# Copy_of_HandHeld_Terminal.net
KiCad netlist of a schematic drawn in Altium Designer
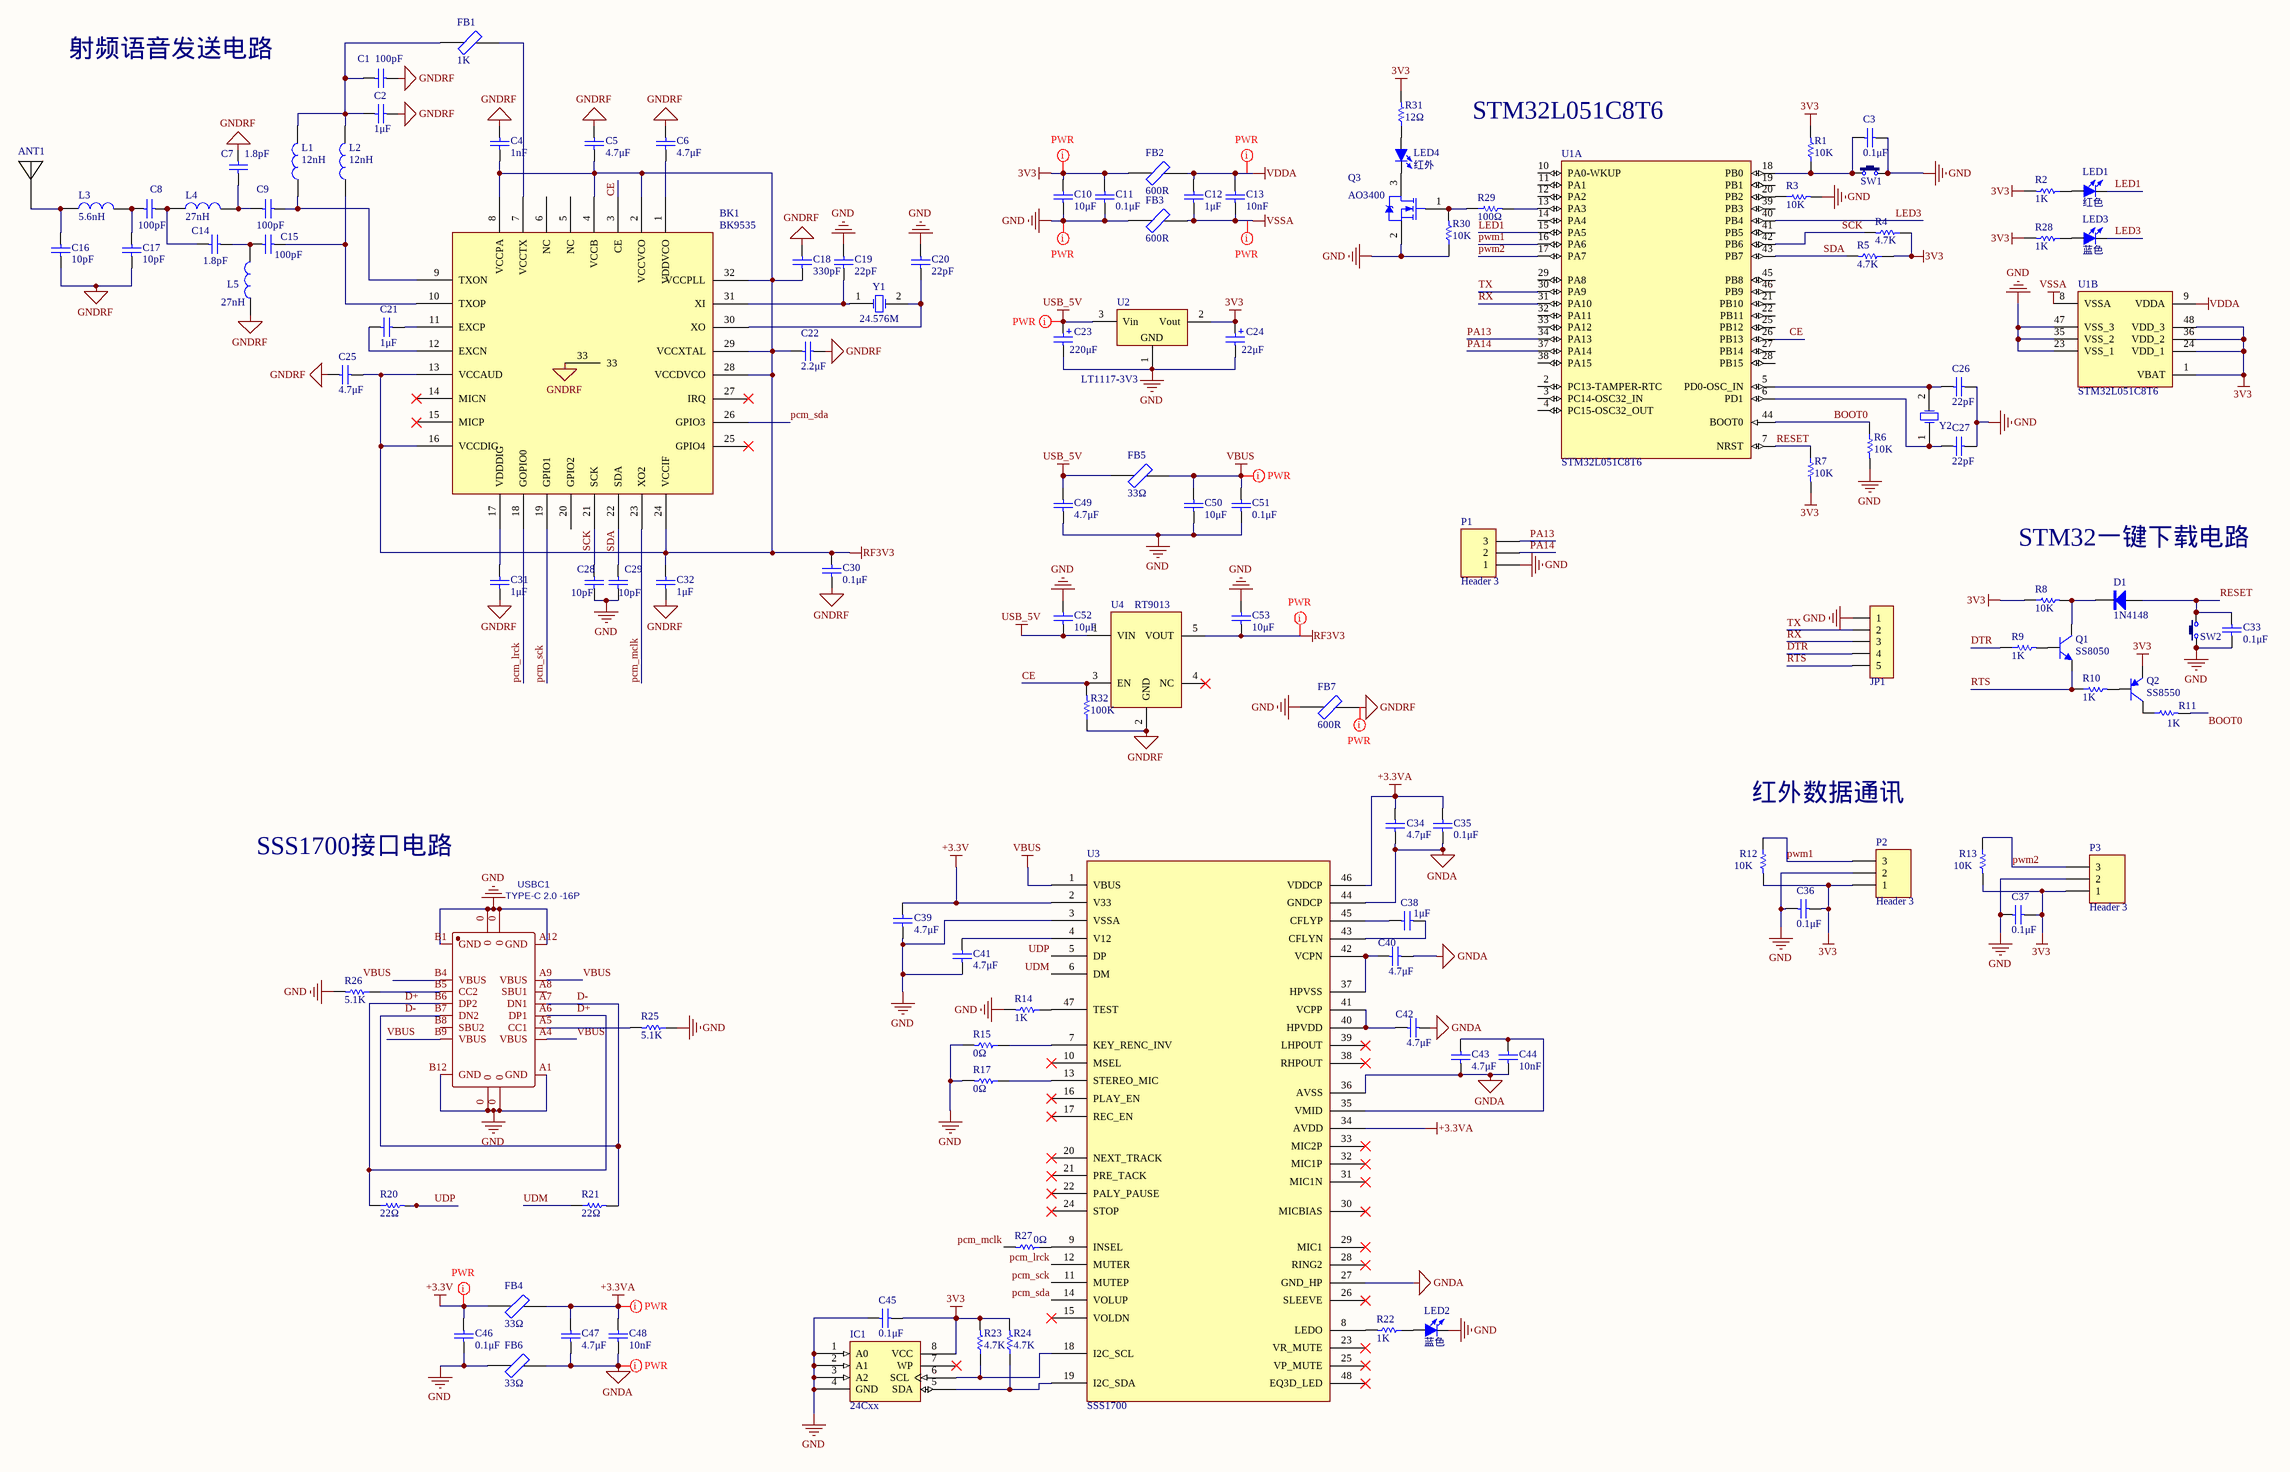
[diagram p0: Copy of HandHeld_Terminal.SchDoc]

(export (version "E")
  (design (tool "Eeschema 10.0.6"))
  (components
    (comp (ref "ANT1")
      (value "~")
      (footprint "ANT")
      (description "PCB板载天线")
      (fields (field (name "版权归属") "源创客"))
      (libsource (lib "手持发射端") (part "ANT1"))
    )
    (comp (ref "BK1") (value "BK9535") (footprint "QFN32 5x5_N") (libsource (lib "Nixie") (part "BK9530")))
    (comp (ref "C1")
      (value "100pF")
      (footprint "C 0603_L")
      (description "Capacitor")
      (fields (field (name "Comment") "Cap") (field (name "PUBLISHER") "Altium Limited"))
      (libsource (lib "Nixie") (part "Cap"))
    )
    (comp (ref "C2")
      (value "1μF")
      (footprint "C 0805_L")
      (description "Capacitor")
      (fields (field (name "Comment") "Cap") (field (name "PUBLISHER") "Altium Limited"))
      (libsource (lib "Nixie") (part "Cap"))
    )
    (comp (ref "C3")
      (value "0.1μF")
      (footprint "C 0805_L")
      (description "Capacitor")
      (fields (field (name "Comment") "Cap") (field (name "PUBLISHER") "Altium Limited"))
      (libsource (lib "Nixie") (part "Cap"))
    )
    (comp (ref "C4")
      (value "1nF")
      (footprint "C 0805_L")
      (description "Capacitor")
      (fields (field (name "Comment") "Cap") (field (name "PUBLISHER") "Altium Limited"))
      (libsource (lib "Nixie") (part "Cap"))
    )
    (comp (ref "C5")
      (value "4.7μF")
      (footprint "C 0805_L")
      (description "Capacitor")
      (fields (field (name "Comment") "Cap") (field (name "PUBLISHER") "Altium Limited"))
      (libsource (lib "Nixie") (part "Cap"))
    )
    (comp (ref "C6")
      (value "4.7μF")
      (footprint "C 0805_L")
      (description "Capacitor")
      (fields (field (name "Comment") "Cap") (field (name "PUBLISHER") "Altium Limited"))
      (libsource (lib "Nixie") (part "Cap"))
    )
    (comp (ref "C7")
      (value "1.8pF")
      (footprint "C 0603_L")
      (description "Capacitor")
      (fields (field (name "Comment") "Cap") (field (name "PUBLISHER") "Altium Limited"))
      (libsource (lib "Nixie") (part "Cap"))
    )
    (comp (ref "C8")
      (value "100pF")
      (footprint "C 0603_L")
      (description "Capacitor")
      (fields (field (name "Comment") "Cap") (field (name "PUBLISHER") "Altium Limited"))
      (libsource (lib "Nixie") (part "Cap"))
    )
    (comp (ref "C9")
      (value "100pF")
      (footprint "C 0603_L")
      (description "Capacitor")
      (fields (field (name "Comment") "Cap") (field (name "PUBLISHER") "Altium Limited"))
      (libsource (lib "Nixie") (part "Cap"))
    )
    (comp (ref "C10")
      (value "10μF")
      (footprint "C 0805_L")
      (description "Capacitor")
      (fields (field (name "Comment") "Cap") (field (name "PUBLISHER") "Altium Limited"))
      (libsource (lib "Nixie") (part "Cap"))
    )
    (comp (ref "C11")
      (value "0.1μF")
      (footprint "C 0805_L")
      (description "Capacitor")
      (fields (field (name "Comment") "Cap") (field (name "PUBLISHER") "Altium Limited"))
      (libsource (lib "Nixie") (part "Cap"))
    )
    (comp (ref "C12")
      (value "1μF")
      (footprint "C 0805_L")
      (description "Capacitor")
      (fields (field (name "Comment") "Cap") (field (name "PUBLISHER") "Altium Limited"))
      (libsource (lib "Nixie") (part "Cap"))
    )
    (comp (ref "C13")
      (value "10nF")
      (footprint "C 0805_L")
      (description "Capacitor")
      (fields (field (name "Comment") "Cap") (field (name "PUBLISHER") "Altium Limited"))
      (libsource (lib "Nixie") (part "Cap"))
    )
    (comp (ref "C14")
      (value "1.8pF")
      (footprint "C 0603_L")
      (description "Capacitor")
      (fields (field (name "Comment") "Cap") (field (name "PUBLISHER") "Altium Limited"))
      (libsource (lib "Nixie") (part "Cap"))
    )
    (comp (ref "C15")
      (value "100pF")
      (footprint "C 0603_L")
      (description "Capacitor")
      (fields (field (name "Comment") "Cap") (field (name "PUBLISHER") "Altium Limited"))
      (libsource (lib "Nixie") (part "Cap"))
    )
    (comp (ref "C16")
      (value "10pF")
      (footprint "C 0603_L")
      (description "Capacitor")
      (fields (field (name "Comment") "Cap") (field (name "PUBLISHER") "Altium Limited"))
      (libsource (lib "Nixie") (part "Cap"))
    )
    (comp (ref "C17")
      (value "10pF")
      (footprint "C 0603_L")
      (description "Capacitor")
      (fields (field (name "Comment") "Cap") (field (name "PUBLISHER") "Altium Limited"))
      (libsource (lib "Nixie") (part "Cap"))
    )
    (comp (ref "C18")
      (value "330pF")
      (footprint "C 0805_L")
      (description "Capacitor")
      (fields (field (name "Comment") "Cap") (field (name "PUBLISHER") "Altium Limited"))
      (libsource (lib "Nixie") (part "Cap"))
    )
    (comp (ref "C19")
      (value "22pF")
      (footprint "C 0805_L")
      (description "Capacitor")
      (fields (field (name "Comment") "Cap") (field (name "PUBLISHER") "Altium Limited"))
      (libsource (lib "Nixie") (part "Cap"))
    )
    (comp (ref "C20")
      (value "22pF")
      (footprint "C 0805_L")
      (description "Capacitor")
      (fields (field (name "Comment") "Cap") (field (name "PUBLISHER") "Altium Limited"))
      (libsource (lib "Nixie") (part "Cap"))
    )
    (comp (ref "C21")
      (value "1μF")
      (footprint "C 0805_L")
      (description "Capacitor")
      (fields (field (name "Comment") "Cap") (field (name "PUBLISHER") "Altium Limited"))
      (libsource (lib "Nixie") (part "Cap"))
    )
    (comp (ref "C22")
      (value "2.2μF")
      (footprint "C 0805_L")
      (description "Capacitor")
      (fields (field (name "Comment") "Cap") (field (name "PUBLISHER") "Altium Limited"))
      (libsource (lib "Nixie") (part "Cap"))
    )
    (comp (ref "C23")
      (value "220μF")
      (footprint "CM D(6.3*5.4)")
      (description "Polarized Capacitor (Radial)")
      (fields (field (name "Comment") "Cap Pol1") (field (name "PUBLISHER") "Altium Limited"))
      (libsource (lib "Nixie") (part "Cap Pol1"))
    )
    (comp (ref "C24")
      (value "22μF")
      (footprint "CD C(6032)")
      (description "Polarized Capacitor (Radial)")
      (fields (field (name "Comment") "Cap Pol1") (field (name "PUBLISHER") "Altium Limited"))
      (libsource (lib "Nixie") (part "Cap Pol1"))
    )
    (comp (ref "C25")
      (value "4.7μF")
      (footprint "C 0805_L")
      (description "Capacitor")
      (fields (field (name "Comment") "Cap") (field (name "PUBLISHER") "Altium Limited"))
      (libsource (lib "Nixie") (part "Cap"))
    )
    (comp (ref "C26")
      (value "22pF")
      (footprint "C 0805_L")
      (description "Capacitor")
      (fields (field (name "Comment") "Cap") (field (name "PUBLISHER") "Altium Limited"))
      (libsource (lib "Nixie") (part "Cap"))
    )
    (comp (ref "C27")
      (value "22pF")
      (footprint "C 0805_L")
      (description "Capacitor")
      (fields (field (name "Comment") "Cap") (field (name "PUBLISHER") "Altium Limited"))
      (libsource (lib "Nixie") (part "Cap"))
    )
    (comp (ref "C28")
      (value "10pF")
      (footprint "C 0603_L")
      (description "Capacitor")
      (fields (field (name "Comment") "Cap") (field (name "PUBLISHER") "Altium Limited"))
      (libsource (lib "Nixie") (part "Cap"))
    )
    (comp (ref "C29")
      (value "10pF")
      (footprint "C 0603_L")
      (description "Capacitor")
      (fields (field (name "Comment") "Cap") (field (name "PUBLISHER") "Altium Limited"))
      (libsource (lib "Nixie") (part "Cap"))
    )
    (comp (ref "C30")
      (value "0.1μF")
      (footprint "C 0805_L")
      (description "Capacitor")
      (fields (field (name "Comment") "Cap") (field (name "PUBLISHER") "Altium Limited"))
      (libsource (lib "Nixie") (part "Cap"))
    )
    (comp (ref "C31")
      (value "1μF")
      (footprint "C 0805_L")
      (description "Capacitor")
      (fields (field (name "Comment") "Cap") (field (name "PUBLISHER") "Altium Limited"))
      (libsource (lib "Nixie") (part "Cap"))
    )
    (comp (ref "C32")
      (value "1μF")
      (footprint "C 0805_L")
      (description "Capacitor")
      (fields (field (name "Comment") "Cap") (field (name "PUBLISHER") "Altium Limited"))
      (libsource (lib "Nixie") (part "Cap"))
    )
    (comp (ref "C33")
      (value "0.1μF")
      (footprint "C 0805_L")
      (description "Capacitor")
      (fields (field (name "Comment") "Cap") (field (name "PUBLISHER") "Altium Limited"))
      (libsource (lib "Nixie") (part "Cap"))
    )
    (comp (ref "C34")
      (value "4.7μF")
      (footprint "C 0805_L")
      (description "Capacitor")
      (fields (field (name "Comment") "Cap") (field (name "PUBLISHER") "Altium Limited"))
      (libsource (lib "Nixie") (part "Cap"))
    )
    (comp (ref "C35")
      (value "0.1μF")
      (footprint "C 0805_L")
      (description "Capacitor")
      (fields (field (name "Comment") "Cap") (field (name "PUBLISHER") "Altium Limited"))
      (libsource (lib "Nixie") (part "Cap"))
    )
    (comp (ref "C36")
      (value "0.1μF")
      (footprint "C 0805_L")
      (description "Capacitor")
      (fields (field (name "Comment") "Cap") (field (name "PUBLISHER") "Altium Limited"))
      (libsource (lib "Nixie") (part "Cap"))
    )
    (comp (ref "C37")
      (value "0.1μF")
      (footprint "C 0805_L")
      (description "Capacitor")
      (fields (field (name "Comment") "Cap") (field (name "PUBLISHER") "Altium Limited"))
      (libsource (lib "Nixie") (part "Cap"))
    )
    (comp (ref "C38")
      (value "1μF")
      (footprint "C 0805_L")
      (description "Capacitor")
      (fields (field (name "Comment") "Cap") (field (name "PUBLISHER") "Altium Limited"))
      (libsource (lib "Nixie") (part "Cap"))
    )
    (comp (ref "C39")
      (value "4.7μF")
      (footprint "C 0805_L")
      (description "Capacitor")
      (fields (field (name "Comment") "Cap") (field (name "PUBLISHER") "Altium Limited"))
      (libsource (lib "Nixie") (part "Cap"))
    )
    (comp (ref "C40")
      (value "4.7μF")
      (footprint "C 0805_L")
      (description "Capacitor")
      (fields (field (name "Comment") "Cap") (field (name "PUBLISHER") "Altium Limited"))
      (libsource (lib "Nixie") (part "Cap"))
    )
    (comp (ref "C41")
      (value "4.7μF")
      (footprint "C 0805_L")
      (description "Capacitor")
      (fields (field (name "Comment") "Cap") (field (name "PUBLISHER") "Altium Limited"))
      (libsource (lib "Nixie") (part "Cap"))
    )
    (comp (ref "C42")
      (value "4.7μF")
      (footprint "C 0805_L")
      (description "Capacitor")
      (fields (field (name "Comment") "Cap") (field (name "PUBLISHER") "Altium Limited"))
      (libsource (lib "Nixie") (part "Cap"))
    )
    (comp (ref "C43")
      (value "4.7μF")
      (footprint "C 0805_L")
      (description "Capacitor")
      (fields (field (name "Comment") "Cap") (field (name "PUBLISHER") "Altium Limited"))
      (libsource (lib "Nixie") (part "Cap"))
    )
    (comp (ref "C44")
      (value "10nF")
      (footprint "C 0805_L")
      (description "Capacitor")
      (fields (field (name "Comment") "Cap") (field (name "PUBLISHER") "Altium Limited"))
      (libsource (lib "Nixie") (part "Cap"))
    )
    (comp (ref "C45")
      (value "0.1μF")
      (footprint "C 0805_L")
      (description "Capacitor")
      (fields (field (name "Comment") "Cap") (field (name "PUBLISHER") "Altium Limited"))
      (libsource (lib "Nixie") (part "Cap"))
    )
    (comp (ref "C46")
      (value "0.1μF")
      (footprint "C 0805_L")
      (description "Capacitor")
      (fields (field (name "Comment") "Cap") (field (name "PUBLISHER") "Altium Limited"))
      (libsource (lib "Nixie") (part "Cap"))
    )
    (comp (ref "C47")
      (value "4.7μF")
      (footprint "C 0805_L")
      (description "Capacitor")
      (fields (field (name "Comment") "Cap") (field (name "PUBLISHER") "Altium Limited"))
      (libsource (lib "Nixie") (part "Cap"))
    )
    (comp (ref "C48")
      (value "10nF")
      (footprint "C 0805_L")
      (description "Capacitor")
      (fields (field (name "Comment") "Cap") (field (name "PUBLISHER") "Altium Limited"))
      (libsource (lib "Nixie") (part "Cap"))
    )
    (comp (ref "C49")
      (value "4.7μF")
      (footprint "C 0805_L")
      (description "Capacitor")
      (fields (field (name "Comment") "Cap") (field (name "PUBLISHER") "Altium Limited"))
      (libsource (lib "Nixie") (part "Cap"))
    )
    (comp (ref "C50")
      (value "10μF")
      (footprint "C 0805_L")
      (description "Capacitor")
      (fields (field (name "Comment") "Cap") (field (name "PUBLISHER") "Altium Limited"))
      (libsource (lib "Nixie") (part "Cap"))
    )
    (comp (ref "C51")
      (value "0.1μF")
      (footprint "C 0805_L")
      (description "Capacitor")
      (fields (field (name "Comment") "Cap") (field (name "PUBLISHER") "Altium Limited"))
      (libsource (lib "Nixie") (part "Cap"))
    )
    (comp (ref "C52")
      (value "10μF")
      (footprint "C 0805_L")
      (description "Capacitor")
      (fields (field (name "Comment") "Cap") (field (name "PUBLISHER") "Altium Limited"))
      (libsource (lib "Nixie") (part "Cap"))
    )
    (comp (ref "C53")
      (value "10μF")
      (footprint "C 0805_L")
      (description "Capacitor")
      (fields (field (name "Comment") "Cap") (field (name "PUBLISHER") "Altium Limited"))
      (libsource (lib "Nixie") (part "Cap"))
    )
    (comp (ref "D1")
      (value "1N4148")
      (footprint "SOD-323")
      (description "开关二极管")
      (libsource (lib "Nixie") (part "1N4148"))
    )
    (comp (ref "FB1")
      (value "1K")
      (footprint "C 0603_L")
      (description "铁氧体磁珠")
      (fields (field (name "Comment") "Ferrite bead"))
      (libsource (lib "Nixie") (part "Ferrite bead"))
    )
    (comp (ref "FB2")
      (value "600R")
      (footprint "C 0603_L")
      (description "铁氧体磁珠")
      (fields (field (name "Comment") "Ferrite bead"))
      (libsource (lib "Nixie") (part "Ferrite bead"))
    )
    (comp (ref "FB3")
      (value "600R")
      (footprint "C 0603_L")
      (description "铁氧体磁珠")
      (fields (field (name "Comment") "Ferrite bead"))
      (libsource (lib "Nixie") (part "Ferrite bead"))
    )
    (comp (ref "FB4")
      (value "33Ω")
      (footprint "C 0603_L")
      (description "铁氧体磁珠")
      (fields (field (name "Comment") "Ferrite bead"))
      (libsource (lib "Nixie") (part "Ferrite bead"))
    )
    (comp (ref "FB5")
      (value "33Ω")
      (footprint "C 0603_L")
      (description "铁氧体磁珠")
      (fields (field (name "Comment") "Ferrite bead"))
      (libsource (lib "Nixie") (part "Ferrite bead"))
    )
    (comp (ref "FB6")
      (value "33Ω")
      (footprint "C 0603_L")
      (description "铁氧体磁珠")
      (fields (field (name "Comment") "Ferrite bead"))
      (libsource (lib "Nixie") (part "Ferrite bead"))
    )
    (comp (ref "FB7")
      (value "600R")
      (footprint "C 0603_L")
      (description "铁氧体磁珠")
      (fields (field (name "Comment") "Ferrite bead"))
      (libsource (lib "Nixie") (part "Ferrite bead"))
    )
    (comp (ref "IC1")
      (value "24Cxx")
      (footprint "SOP8_L")
      (description "外置EEPROM")
      (fields (field (name "版权归属") "封装库来自淘宝 ID：黄晶宝石"))
      (libsource (lib "Nixie") (part "24Cxx"))
    )
    (comp (ref "JP1")
      (value "HDR-1X5")
      (footprint "HDR2.0-LI-5P")
      (description "5P接插件")
      (fields (field (name "版权归属") "封装库来自淘宝 ID：黄晶宝石"))
      (libsource (lib "Nixie") (part "Header 5"))
    )
    (comp (ref "L1")
      (value "12nH")
      (footprint "L 0603")
      (description "小功率贴片电感")
      (fields (field (name "Comment") "L"))
      (libsource (lib "Nixie") (part "L"))
    )
    (comp (ref "L2")
      (value "12nH")
      (footprint "L 0603")
      (description "小功率贴片电感")
      (fields (field (name "Comment") "L"))
      (libsource (lib "Nixie") (part "L"))
    )
    (comp (ref "L3")
      (value "5.6nH")
      (footprint "L 0603")
      (description "小功率贴片电感")
      (fields (field (name "Comment") "L"))
      (libsource (lib "Nixie") (part "L"))
    )
    (comp (ref "L4")
      (value "27nH")
      (footprint "L 0603")
      (description "小功率贴片电感")
      (fields (field (name "Comment") "L"))
      (libsource (lib "Nixie") (part "L"))
    )
    (comp (ref "L5")
      (value "27nH")
      (footprint "L 0603")
      (description "小功率贴片电感")
      (fields (field (name "Comment") "L"))
      (libsource (lib "Nixie") (part "L"))
    )
    (comp (ref "LED1")
      (value "红色")
      (footprint "LED 0805R")
      (description "贴片LED")
      (fields (field (name "版权归属") "封装库来自淘宝 ID：黄晶宝石"))
      (libsource (lib "Nixie") (part "LED-SMD"))
    )
    (comp (ref "LED2")
      (value "蓝色")
      (footprint "LED 0805B")
      (description "贴片LED")
      (fields (field (name "版权归属") "封装库来自淘宝 ID：黄晶宝石"))
      (libsource (lib "Nixie") (part "LED-SMD"))
    )
    (comp (ref "LED3")
      (value "蓝色")
      (footprint "LED 0805B")
      (description "贴片LED")
      (fields (field (name "版权归属") "封装库来自淘宝 ID：黄晶宝石"))
      (libsource (lib "Nixie") (part "LED-SMD"))
    )
    (comp (ref "LED4")
      (value "红外")
      (footprint "LED 3MM-R")
      (description "贴片LED")
      (fields (field (name "版权归属") "封装库来自淘宝 ID：黄晶宝石"))
      (libsource (lib "Nixie") (part "LED-SMD"))
    )
    (comp (ref "P1")
      (value "Header 3")
      (footprint "HDR1X3")
      (description "Header, 3-Pin")
      (fields (field (name "PUBLISHER") "Altium Limited"))
      (libsource (lib "Miscellaneous Connectors") (part "Header 3"))
    )
    (comp (ref "P2")
      (value "Header 3")
      (footprint "HDR1X3")
      (description "Header, 3-Pin")
      (fields (field (name "PUBLISHER") "Altium Limited"))
      (libsource (lib "") (part "Header 3_1"))
    )
    (comp (ref "P3")
      (value "Header 3")
      (footprint "HDR1X3")
      (description "Header, 3-Pin")
      (fields (field (name "PUBLISHER") "Altium Limited"))
      (libsource (lib "") (part "Header 3_1"))
    )
    (comp (ref "Q1")
      (value "SS8050")
      (footprint "SOT-23-3L")
      (description "高频放大-NPN型")
      (fields (field (name "版权归属") "封装库来自淘宝 ID：黄晶宝石"))
      (libsource (lib "Nixie") (part "8050-SMD"))
    )
    (comp (ref "Q2")
      (value "SS8550")
      (footprint "SOT-23-3L")
      (description "高频放大-PNP型")
      (fields (field (name "版权归属") "封装库来自淘宝 ID：黄晶宝石"))
      (libsource (lib "Nixie") (part "8550-SMD"))
    )
    (comp (ref "Q3")
      (value "AO3400")
      (footprint "SOT-23-3L")
      (description "N-Channel Power MOSFET")
      (fields (field (name "PUBLISHER") "Altium Limited"))
      (libsource (lib "Nixie") (part "NMOS-2"))
    )
    (comp (ref "R1")
      (value "10K")
      (footprint "R 0805_L")
      (description "Resistor")
      (fields (field (name "PUBLISHER") "Altium Limited"))
      (libsource (lib "Nixie") (part "Resistor"))
    )
    (comp (ref "R2")
      (value "1K")
      (footprint "R 0805_L")
      (description "Resistor")
      (fields (field (name "PUBLISHER") "Altium Limited"))
      (libsource (lib "Nixie") (part "Resistor"))
    )
    (comp (ref "R3")
      (value "10K")
      (footprint "R 0805_L")
      (description "Resistor")
      (fields (field (name "PUBLISHER") "Altium Limited"))
      (libsource (lib "Nixie") (part "Resistor"))
    )
    (comp (ref "R4")
      (value "4.7K")
      (footprint "R 0805_L")
      (description "Resistor")
      (fields (field (name "PUBLISHER") "Altium Limited"))
      (libsource (lib "Nixie") (part "Resistor"))
    )
    (comp (ref "R5")
      (value "4.7K")
      (footprint "R 0805_L")
      (description "Resistor")
      (fields (field (name "PUBLISHER") "Altium Limited"))
      (libsource (lib "Nixie") (part "Resistor"))
    )
    (comp (ref "R6")
      (value "10K")
      (footprint "R 0805_L")
      (description "Resistor")
      (fields (field (name "PUBLISHER") "Altium Limited"))
      (libsource (lib "Nixie") (part "Resistor"))
    )
    (comp (ref "R7")
      (value "10K")
      (footprint "R 0805_L")
      (description "Resistor")
      (fields (field (name "PUBLISHER") "Altium Limited"))
      (libsource (lib "Nixie") (part "Resistor"))
    )
    (comp (ref "R8")
      (value "10K")
      (footprint "R 0805_L")
      (description "Resistor")
      (fields (field (name "PUBLISHER") "Altium Limited"))
      (libsource (lib "Nixie") (part "Resistor"))
    )
    (comp (ref "R9")
      (value "1K")
      (footprint "R 0805_L")
      (description "Resistor")
      (fields (field (name "PUBLISHER") "Altium Limited"))
      (libsource (lib "Nixie") (part "Resistor"))
    )
    (comp (ref "R10")
      (value "1K")
      (footprint "R 0805_L")
      (description "Resistor")
      (fields (field (name "PUBLISHER") "Altium Limited"))
      (libsource (lib "Nixie") (part "Resistor"))
    )
    (comp (ref "R11")
      (value "1K")
      (footprint "R 0805_L")
      (description "Resistor")
      (fields (field (name "PUBLISHER") "Altium Limited"))
      (libsource (lib "Nixie") (part "Resistor"))
    )
    (comp (ref "R12")
      (value "10K")
      (footprint "R 0805_L")
      (description "Resistor")
      (fields (field (name "PUBLISHER") "Altium Limited"))
      (libsource (lib "Nixie") (part "Resistor"))
    )
    (comp (ref "R13")
      (value "10K")
      (footprint "R 0805_L")
      (description "Resistor")
      (fields (field (name "PUBLISHER") "Altium Limited"))
      (libsource (lib "Nixie") (part "Resistor"))
    )
    (comp (ref "R14")
      (value "1K")
      (footprint "R 0805_L")
      (description "Resistor")
      (fields (field (name "PUBLISHER") "Altium Limited"))
      (libsource (lib "Nixie") (part "Resistor"))
    )
    (comp (ref "R15")
      (value "0Ω")
      (footprint "R 0603_L")
      (description "Resistor")
      (fields (field (name "PUBLISHER") "Altium Limited"))
      (libsource (lib "Nixie") (part "Resistor"))
    )
    (comp (ref "R17")
      (value "0Ω")
      (footprint "R 0603_L")
      (description "Resistor")
      (fields (field (name "PUBLISHER") "Altium Limited"))
      (libsource (lib "Nixie") (part "Resistor"))
    )
    (comp (ref "R20")
      (value "22Ω")
      (footprint "R 0603_L")
      (description "Resistor")
      (fields (field (name "PUBLISHER") "Altium Limited"))
      (libsource (lib "Nixie") (part "Resistor"))
    )
    (comp (ref "R21")
      (value "22Ω")
      (footprint "R 0603_L")
      (description "Resistor")
      (fields (field (name "PUBLISHER") "Altium Limited"))
      (libsource (lib "Nixie") (part "Resistor"))
    )
    (comp (ref "R22")
      (value "1K")
      (footprint "R 0805_L")
      (description "Resistor")
      (fields (field (name "PUBLISHER") "Altium Limited"))
      (libsource (lib "Nixie") (part "Resistor"))
    )
    (comp (ref "R23")
      (value "4.7K")
      (footprint "R 0805_L")
      (description "Resistor")
      (fields (field (name "PUBLISHER") "Altium Limited"))
      (libsource (lib "Nixie") (part "Resistor"))
    )
    (comp (ref "R24")
      (value "4.7K")
      (footprint "R 0805_L")
      (description "Resistor")
      (fields (field (name "PUBLISHER") "Altium Limited"))
      (libsource (lib "Nixie") (part "Resistor"))
    )
    (comp (ref "R25")
      (value "5.1K")
      (footprint "R 0805_L")
      (description "Resistor")
      (fields (field (name "PUBLISHER") "Altium Limited"))
      (libsource (lib "Nixie") (part "Resistor"))
    )
    (comp (ref "R26")
      (value "5.1K")
      (footprint "R 0805_L")
      (description "Resistor")
      (fields (field (name "PUBLISHER") "Altium Limited"))
      (libsource (lib "Nixie") (part "Resistor"))
    )
    (comp (ref "R27")
      (value "0Ω")
      (footprint "R 0603_L")
      (description "Resistor")
      (fields (field (name "PUBLISHER") "Altium Limited"))
      (libsource (lib "Nixie") (part "Resistor"))
    )
    (comp (ref "R28")
      (value "1K")
      (footprint "R 0805_L")
      (description "Resistor")
      (fields (field (name "PUBLISHER") "Altium Limited"))
      (libsource (lib "Nixie") (part "Resistor"))
    )
    (comp (ref "R29")
      (value "100Ω")
      (footprint "R 0805_L")
      (description "Resistor")
      (fields (field (name "PUBLISHER") "Altium Limited"))
      (libsource (lib "Nixie") (part "Resistor"))
    )
    (comp (ref "R30")
      (value "10K")
      (footprint "R 0805_L")
      (description "Resistor")
      (fields (field (name "PUBLISHER") "Altium Limited"))
      (libsource (lib "Nixie") (part "Resistor"))
    )
    (comp (ref "R31")
      (value "12Ω")
      (footprint "R 1210_L")
      (description "Resistor")
      (fields (field (name "PUBLISHER") "Altium Limited"))
      (libsource (lib "Nixie") (part "Resistor"))
    )
    (comp (ref "R32")
      (value "100K")
      (footprint "R 0805_L")
      (description "Resistor")
      (fields (field (name "PUBLISHER") "Altium Limited"))
      (libsource (lib "Nixie") (part "Resistor"))
    )
    (comp (ref "SW1")
      (value "3x6x5")
      (footprint "TSW SMD-3*6*2.5")
      (description "3x6轻触开关")
      (fields (field (name "版权归属") "封装库来自淘宝 ID：黄晶宝石"))
      (libsource (lib "") (part "TSW 3x6_1"))
    )
    (comp (ref "SW2")
      (value "3x6x5")
      (footprint "TSW SMD-3*6*2.5")
      (description "3x6轻触开关")
      (fields (field (name "版权归属") "封装库来自淘宝 ID：黄晶宝石"))
      (libsource (lib "Nixie") (part "TSW 3x6"))
    )
    (comp (ref "U1")
      (value "STM32L051C8T6")
      (footprint "LQFP48_L")
      (description "ARM")
      (libsource (lib "Nixie") (part "STM32F103C8T6"))
    )
    (comp (ref "U2")
      (value "LT1117-3V3")
      (footprint "SOT223_L")
      (description "三端稳压芯片")
      (fields (field (name "版权归属") "源创客"))
      (libsource (lib "Nixie") (part "LT1117"))
    )
    (comp (ref "U3")
      (value "SSS1700")
      (footprint "LQFP48_L")
      (description "USB音频芯片")
      (libsource (lib "Nixie") (part "SSS1700"))
    )
    (comp (ref "U4")
      (value "RT9013")
      (footprint "SOT23-5L")
      (description "LDO")
      (libsource (lib "HandHeld_terminal") (part "RT9013"))
    )
    (comp (ref "USBC1")
      (value "TYPE-C 2.0 -16P")
      (footprint "USB-C-SMD_TYPE-C-USB-5")
      (description "USB2.0 Type-C 母座 16Pin")
      (libsource (lib "Nixie") (part "USB2.0 Type-C 16Pin母座"))
    )
    (comp (ref "Y1")
      (value "24.576M")
      (footprint "OSC 5032-2P")
      (description "Crystal Oscillator")
      (fields (field (name "PUBLISHER") "Altium Limited"))
      (libsource (lib "Miscellaneous Devices") (part "XTAL"))
    )
    (comp (ref "Y2")
      (value "8MHz ±20ppm 20pF")
      (footprint "OSC 5032-2P")
      (description "贴片晶振")
      (libsource (lib "HandHeld_terminal") (part "SMD-5032_2P 8MHz 20ppm 20pF"))
    )
  )
  (nets
    (net (code "1") (name "+3.3V") (class "Default")
      (node (ref "C39") (pin "2") (pinfunction "2_2") (pintype "passive"))
      (node (ref "C46") (pin "2") (pinfunction "2_2") (pintype "passive"))
      (node (ref "FB4") (pin "1") (pinfunction "1_1") (pintype "passive"))
      (node (ref "U3") (pin "2") (pinfunction "V33_2") (pintype "passive"))
    )
    (net (code "2") (name "+3.3VA") (class "Default")
      (node (ref "C34") (pin "2") (pinfunction "2_2") (pintype "passive"))
      (node (ref "C35") (pin "2") (pinfunction "2_2") (pintype "passive"))
      (node (ref "C47") (pin "2") (pinfunction "2_2") (pintype "passive"))
      (node (ref "C48") (pin "2") (pinfunction "2_2") (pintype "passive"))
      (node (ref "FB4") (pin "2") (pinfunction "2_2") (pintype "passive"))
      (node (ref "U3") (pin "34") (pinfunction "AVDD_34") (pintype "passive"))
      (node (ref "U3") (pin "46") (pinfunction "VDDCP_46") (pintype "passive"))
    )
    (net (code "3") (name "/BOOT0") (class "Default")
      (node (ref "R11") (pin "2") (pinfunction "2_2") (pintype "passive"))
      (node (ref "R6") (pin "1") (pinfunction "1_1") (pintype "passive"))
      (node (ref "U1") (pin "44") (pinfunction "BOOT0_44") (pintype "input"))
    )
    (net (code "4") (name "/CE") (class "Default")
      (node (ref "BK1") (pin "3") (pinfunction "CE_3") (pintype "passive"))
      (node (ref "R32") (pin "2") (pinfunction "2_2") (pintype "passive"))
      (node (ref "U1") (pin "26") (pinfunction "PB13_26") (pintype "bidirectional"))
      (node (ref "U4") (pin "3") (pinfunction "EN_3") (pintype "passive"))
    )
    (net (code "5") (name "/D+") (class "Default")
      (node (ref "R20") (pin "1") (pinfunction "1_1") (pintype "passive"))
      (node (ref "USBC1") (pin "A6") (pinfunction "DP1_A6") (pintype "passive"))
      (node (ref "USBC1") (pin "B6") (pinfunction "DP2_B6") (pintype "passive"))
    )
    (net (code "6") (name "/D-") (class "Default")
      (node (ref "R21") (pin "2") (pinfunction "2_2") (pintype "passive"))
      (node (ref "USBC1") (pin "A7") (pinfunction "DN1_A7") (pintype "passive"))
      (node (ref "USBC1") (pin "B7") (pinfunction "DN2_B7") (pintype "passive"))
    )
    (net (code "7") (name "/DTR") (class "Default")
      (node (ref "JP1") (pin "4") (pinfunction "4_4") (pintype "passive"))
      (node (ref "R9") (pin "1") (pinfunction "1_1") (pintype "passive"))
    )
    (net (code "8") (name "/LED1") (class "Default")
      (node (ref "LED1") (pin "2") (pinfunction "K_2") (pintype "passive"))
      (node (ref "U1") (pin "15") (pinfunction "PA5_15") (pintype "bidirectional"))
    )
    (net (code "9") (name "/LED3") (class "Default")
      (node (ref "LED3") (pin "2") (pinfunction "K_2") (pintype "passive"))
      (node (ref "U1") (pin "40") (pinfunction "PB4_40") (pintype "bidirectional"))
    )
    (net (code "10") (name "/PA13") (class "Default")
      (node (ref "P1") (pin "3") (pinfunction "3_3") (pintype "passive"))
      (node (ref "U1") (pin "34") (pinfunction "PA13_34") (pintype "bidirectional"))
    )
    (net (code "11") (name "/PA14") (class "Default")
      (node (ref "P1") (pin "2") (pinfunction "2_2") (pintype "passive"))
      (node (ref "U1") (pin "37") (pinfunction "PA14_37") (pintype "bidirectional"))
    )
    (net (code "12") (name "/RESET") (class "Default")
      (node (ref "C33") (pin "2") (pinfunction "2_2") (pintype "passive"))
      (node (ref "D1") (pin "1") (pinfunction "A_1") (pintype "passive"))
      (node (ref "R7") (pin "1") (pinfunction "1_1") (pintype "passive"))
      (node (ref "SW2") (pin "2") (pinfunction "2_2") (pintype "passive"))
      (node (ref "U1") (pin "7") (pinfunction "NRST_7") (pintype "bidirectional"))
    )
    (net (code "13") (name "/RTS") (class "Default")
      (node (ref "JP1") (pin "5") (pinfunction "5_5") (pintype "passive"))
      (node (ref "Q1") (pin "2") (pinfunction "E_2") (pintype "passive"))
      (node (ref "R10") (pin "1") (pinfunction "1_1") (pintype "passive"))
    )
    (net (code "14") (name "/RX") (class "Default")
      (node (ref "JP1") (pin "3") (pinfunction "3_3") (pintype "passive"))
      (node (ref "U1") (pin "31") (pinfunction "PA10_31") (pintype "bidirectional"))
    )
    (net (code "15") (name "/SCK") (class "Default")
      (node (ref "BK1") (pin "21") (pinfunction "SCK_21") (pintype "passive"))
      (node (ref "C28") (pin "2") (pinfunction "2_2") (pintype "passive"))
      (node (ref "R4") (pin "2") (pinfunction "2_2") (pintype "passive"))
      (node (ref "U1") (pin "42") (pinfunction "PB6_42") (pintype "bidirectional"))
    )
    (net (code "16") (name "/SDA") (class "Default")
      (node (ref "BK1") (pin "22") (pinfunction "SDA_22") (pintype "passive"))
      (node (ref "C29") (pin "2") (pinfunction "2_2") (pintype "passive"))
      (node (ref "R5") (pin "2") (pinfunction "2_2") (pintype "passive"))
      (node (ref "U1") (pin "43") (pinfunction "PB7_43") (pintype "bidirectional"))
    )
    (net (code "17") (name "/TX") (class "Default")
      (node (ref "JP1") (pin "2") (pinfunction "2_2") (pintype "passive"))
      (node (ref "U1") (pin "30") (pinfunction "PA9_30") (pintype "bidirectional"))
    )
    (net (code "18") (name "/UDM") (class "Default")
      (node (ref "R21") (pin "1") (pinfunction "1_1") (pintype "passive"))
      (node (ref "U3") (pin "6") (pinfunction "DM_6") (pintype "passive"))
    )
    (net (code "19") (name "/UDP") (class "Default")
      (node (ref "R20") (pin "2") (pinfunction "2_2") (pintype "passive"))
      (node (ref "U3") (pin "5") (pinfunction "DP_5") (pintype "passive"))
    )
    (net (code "20") (name "/pcm_lrck") (class "Default")
      (node (ref "BK1") (pin "18") (pinfunction "GOPIO0_18") (pintype "passive"))
      (node (ref "U3") (pin "12") (pinfunction "MUTER_12") (pintype "passive"))
    )
    (net (code "21") (name "/pcm_mclk") (class "Default")
      (node (ref "BK1") (pin "23") (pinfunction "XO2_23") (pintype "passive"))
      (node (ref "R27") (pin "2") (pinfunction "2_2") (pintype "passive"))
    )
    (net (code "22") (name "/pcm_sck") (class "Default")
      (node (ref "BK1") (pin "19") (pinfunction "GPIO1_19") (pintype "passive"))
      (node (ref "U3") (pin "11") (pinfunction "MUTEP_11") (pintype "passive"))
    )
    (net (code "23") (name "/pcm_sda") (class "Default")
      (node (ref "BK1") (pin "26") (pinfunction "GPIO3_26") (pintype "passive"))
      (node (ref "U3") (pin "14") (pinfunction "VOLUP_14") (pintype "passive"))
    )
    (net (code "24") (name "/pwm1") (class "Default")
      (node (ref "P2") (pin "3") (pinfunction "3_3") (pintype "passive"))
      (node (ref "R12") (pin "1") (pinfunction "1_1") (pintype "passive"))
      (node (ref "U1") (pin "16") (pinfunction "PA6_16") (pintype "bidirectional"))
    )
    (net (code "25") (name "/pwm2") (class "Default")
      (node (ref "P3") (pin "3") (pinfunction "3_3") (pintype "passive"))
      (node (ref "R13") (pin "1") (pinfunction "1_1") (pintype "passive"))
      (node (ref "U1") (pin "17") (pinfunction "PA7_17") (pintype "bidirectional"))
    )
    (net (code "26") (name "3V3") (class "Default")
      (node (ref "C10") (pin "2") (pinfunction "2_2") (pintype "passive"))
      (node (ref "C11") (pin "2") (pinfunction "2_2") (pintype "passive"))
      (node (ref "C24") (pin "1") (pinfunction "1_1") (pintype "passive"))
      (node (ref "C36") (pin "1") (pinfunction "1_1") (pintype "passive"))
      (node (ref "C37") (pin "1") (pinfunction "1_1") (pintype "passive"))
      (node (ref "C45") (pin "1") (pinfunction "1_1") (pintype "passive"))
      (node (ref "FB2") (pin "1") (pinfunction "1_1") (pintype "passive"))
      (node (ref "IC1") (pin "8") (pinfunction "VCC_8") (pintype "power_in"))
      (node (ref "P2") (pin "1") (pinfunction "1_1") (pintype "passive"))
      (node (ref "P3") (pin "1") (pinfunction "1_1") (pintype "passive"))
      (node (ref "Q2") (pin "2") (pinfunction "E_2") (pintype "passive"))
      (node (ref "R1") (pin "2") (pinfunction "2_2") (pintype "passive"))
      (node (ref "R12") (pin "2") (pinfunction "2_2") (pintype "passive"))
      (node (ref "R13") (pin "2") (pinfunction "2_2") (pintype "passive"))
      (node (ref "R2") (pin "2") (pinfunction "2_2") (pintype "passive"))
      (node (ref "R23") (pin "2") (pinfunction "2_2") (pintype "passive"))
      (node (ref "R24") (pin "2") (pinfunction "2_2") (pintype "passive"))
      (node (ref "R28") (pin "2") (pinfunction "2_2") (pintype "passive"))
      (node (ref "R31") (pin "2") (pinfunction "2_2") (pintype "passive"))
      (node (ref "R4") (pin "1") (pinfunction "1_1") (pintype "passive"))
      (node (ref "R5") (pin "1") (pinfunction "1_1") (pintype "passive"))
      (node (ref "R7") (pin "2") (pinfunction "2_2") (pintype "passive"))
      (node (ref "R8") (pin "1") (pinfunction "1_1") (pintype "passive"))
      (node (ref "U1") (pin "1") (pinfunction "VBAT_1") (pintype "power_in"))
      (node (ref "U1") (pin "24") (pinfunction "VDD_1_24") (pintype "power_in"))
      (node (ref "U1") (pin "36") (pinfunction "VDD_2_36") (pintype "power_in"))
      (node (ref "U1") (pin "48") (pinfunction "VDD_3_48") (pintype "power_in"))
      (node (ref "U2") (pin "2") (pinfunction "Vout_2") (pintype "passive"))
    )
    (net (code "27") (name "GND") (class "Default")
      (node (ref "C10") (pin "1") (pinfunction "1_1") (pintype "passive"))
      (node (ref "C11") (pin "1") (pinfunction "1_1") (pintype "passive"))
      (node (ref "C19") (pin "2") (pinfunction "2_2") (pintype "passive"))
      (node (ref "C20") (pin "2") (pinfunction "2_2") (pintype "passive"))
      (node (ref "C23") (pin "2") (pinfunction "2_2") (pintype "passive"))
      (node (ref "C24") (pin "2") (pinfunction "2_2") (pintype "passive"))
      (node (ref "C26") (pin "1") (pinfunction "1_1") (pintype "passive"))
      (node (ref "C27") (pin "1") (pinfunction "1_1") (pintype "passive"))
      (node (ref "C28") (pin "1") (pinfunction "1_1") (pintype "passive"))
      (node (ref "C29") (pin "1") (pinfunction "1_1") (pintype "passive"))
      (node (ref "C3") (pin "1") (pinfunction "1_1") (pintype "passive"))
      (node (ref "C33") (pin "1") (pinfunction "1_1") (pintype "passive"))
      (node (ref "C36") (pin "2") (pinfunction "2_2") (pintype "passive"))
      (node (ref "C37") (pin "2") (pinfunction "2_2") (pintype "passive"))
      (node (ref "C39") (pin "1") (pinfunction "1_1") (pintype "passive"))
      (node (ref "C41") (pin "1") (pinfunction "1_1") (pintype "passive"))
      (node (ref "C45") (pin "2") (pinfunction "2_2") (pintype "passive"))
      (node (ref "C46") (pin "1") (pinfunction "1_1") (pintype "passive"))
      (node (ref "C49") (pin "1") (pinfunction "1_1") (pintype "passive"))
      (node (ref "C50") (pin "1") (pinfunction "1_1") (pintype "passive"))
      (node (ref "C51") (pin "1") (pinfunction "1_1") (pintype "passive"))
      (node (ref "C52") (pin "2") (pinfunction "2_2") (pintype "passive"))
      (node (ref "C53") (pin "2") (pinfunction "2_2") (pintype "passive"))
      (node (ref "FB3") (pin "1") (pinfunction "1_1") (pintype "passive"))
      (node (ref "FB6") (pin "1") (pinfunction "1_1") (pintype "passive"))
      (node (ref "FB7") (pin "1") (pinfunction "1_1") (pintype "passive"))
      (node (ref "IC1") (pin "1") (pinfunction "A0_1") (pintype "input"))
      (node (ref "IC1") (pin "2") (pinfunction "A1_2") (pintype "input"))
      (node (ref "IC1") (pin "3") (pinfunction "A2_3") (pintype "input"))
      (node (ref "IC1") (pin "4") (pinfunction "GND_4") (pintype "passive"))
      (node (ref "JP1") (pin "1") (pinfunction "1_1") (pintype "passive"))
      (node (ref "LED2") (pin "2") (pinfunction "K_2") (pintype "passive"))
      (node (ref "P1") (pin "1") (pinfunction "1_1") (pintype "passive"))
      (node (ref "P2") (pin "2") (pinfunction "2_2") (pintype "passive"))
      (node (ref "P3") (pin "2") (pinfunction "2_2") (pintype "passive"))
      (node (ref "Q3") (pin "2") (pinfunction "S_2") (pintype "passive"))
      (node (ref "R14") (pin "2") (pinfunction "2_2") (pintype "passive"))
      (node (ref "R15") (pin "2") (pinfunction "2_2") (pintype "passive"))
      (node (ref "R17") (pin "2") (pinfunction "2_2") (pintype "passive"))
      (node (ref "R25") (pin "1") (pinfunction "1_1") (pintype "passive"))
      (node (ref "R26") (pin "2") (pinfunction "2_2") (pintype "passive"))
      (node (ref "R3") (pin "2") (pinfunction "2_2") (pintype "passive"))
      (node (ref "R30") (pin "1") (pinfunction "1_1") (pintype "passive"))
      (node (ref "R6") (pin "2") (pinfunction "2_2") (pintype "passive"))
      (node (ref "SW1") (pin "2") (pinfunction "2_2") (pintype "passive"))
      (node (ref "SW2") (pin "1") (pinfunction "1_1") (pintype "passive"))
      (node (ref "U1") (pin "23") (pinfunction "VSS_1_23") (pintype "power_in"))
      (node (ref "U1") (pin "35") (pinfunction "VSS_2_35") (pintype "power_in"))
      (node (ref "U1") (pin "47") (pinfunction "VSS_3_47") (pintype "power_in"))
      (node (ref "U2") (pin "1") (pinfunction "GND_1") (pintype "passive"))
      (node (ref "U3") (pin "3") (pinfunction "VSSA_3") (pintype "passive"))
      (node (ref "USBC1") (pin "0") (pinfunction "0_0") (pintype "passive"))
      (node (ref "USBC1") (pin "A1") (pinfunction "GND_A1") (pintype "passive"))
      (node (ref "USBC1") (pin "A12") (pinfunction "GND_A12") (pintype "passive"))
      (node (ref "USBC1") (pin "B1") (pinfunction "GND_B1") (pintype "passive"))
      (node (ref "USBC1") (pin "B12") (pinfunction "GND_B12") (pintype "passive"))
    )
    (net (code "28") (name "GNDA") (class "Default")
      (node (ref "C34") (pin "1") (pinfunction "1_1") (pintype "passive"))
      (node (ref "C35") (pin "1") (pinfunction "1_1") (pintype "passive"))
      (node (ref "C40") (pin "1") (pinfunction "1_1") (pintype "passive"))
      (node (ref "C42") (pin "1") (pinfunction "1_1") (pintype "passive"))
      (node (ref "C43") (pin "1") (pinfunction "1_1") (pintype "passive"))
      (node (ref "C44") (pin "1") (pinfunction "1_1") (pintype "passive"))
      (node (ref "C47") (pin "1") (pinfunction "1_1") (pintype "passive"))
      (node (ref "C48") (pin "1") (pinfunction "1_1") (pintype "passive"))
      (node (ref "FB6") (pin "2") (pinfunction "2_2") (pintype "passive"))
      (node (ref "U3") (pin "27") (pinfunction "GND_HP_27") (pintype "passive"))
      (node (ref "U3") (pin "36") (pinfunction "AVSS_36") (pintype "passive"))
      (node (ref "U3") (pin "44") (pinfunction "GNDCP_44") (pintype "passive"))
    )
    (net (code "29") (name "GNDRF") (class "Default")
      (node (ref "BK1") (pin "33") (pinfunction "33_33") (pintype "passive"))
      (node (ref "C1") (pin "1") (pinfunction "1_1") (pintype "passive"))
      (node (ref "C16") (pin "2") (pinfunction "2_2") (pintype "passive"))
      (node (ref "C17") (pin "2") (pinfunction "2_2") (pintype "passive"))
      (node (ref "C18") (pin "2") (pinfunction "2_2") (pintype "passive"))
      (node (ref "C2") (pin "1") (pinfunction "1_1") (pintype "passive"))
      (node (ref "C22") (pin "1") (pinfunction "1_1") (pintype "passive"))
      (node (ref "C25") (pin "2") (pinfunction "2_2") (pintype "passive"))
      (node (ref "C30") (pin "1") (pinfunction "1_1") (pintype "passive"))
      (node (ref "C31") (pin "1") (pinfunction "1_1") (pintype "passive"))
      (node (ref "C32") (pin "1") (pinfunction "1_1") (pintype "passive"))
      (node (ref "C4") (pin "1") (pinfunction "1_1") (pintype "passive"))
      (node (ref "C5") (pin "1") (pinfunction "1_1") (pintype "passive"))
      (node (ref "C6") (pin "1") (pinfunction "1_1") (pintype "passive"))
      (node (ref "C7") (pin "1") (pinfunction "1_1") (pintype "passive"))
      (node (ref "FB7") (pin "2") (pinfunction "2_2") (pintype "passive"))
      (node (ref "L5") (pin "1") (pinfunction "1_1") (pintype "passive"))
      (node (ref "R32") (pin "1") (pinfunction "1_1") (pintype "passive"))
      (node (ref "U4") (pin "2") (pinfunction "GND_2") (pintype "passive"))
    )
    (net (code "30") (name "Net-(ANT1-Pad1)") (class "Default")
      (node (ref "ANT1") (pin "1") (pinfunction "1_1") (pintype "passive"))
      (node (ref "C16") (pin "1") (pinfunction "1_1") (pintype "passive"))
      (node (ref "L3") (pin "1") (pinfunction "1_1") (pintype "passive"))
    )
    (net (code "31") (name "Net-(BK1-EXCN)") (class "Default")
      (node (ref "BK1") (pin "12") (pinfunction "EXCN_12") (pintype "passive"))
      (node (ref "C21") (pin "2") (pinfunction "2_2") (pintype "passive"))
    )
    (net (code "32") (name "Net-(BK1-EXCP)") (class "Default")
      (node (ref "BK1") (pin "11") (pinfunction "EXCP_11") (pintype "passive"))
      (node (ref "C21") (pin "1") (pinfunction "1_1") (pintype "passive"))
    )
    (net (code "33") (name "Net-(BK1-TXON)") (class "Default")
      (node (ref "BK1") (pin "9") (pinfunction "TXON_9") (pintype "passive"))
      (node (ref "C9") (pin "1") (pinfunction "1_1") (pintype "passive"))
      (node (ref "L1") (pin "1") (pinfunction "1_1") (pintype "passive"))
    )
    (net (code "34") (name "Net-(BK1-TXOP)") (class "Default")
      (node (ref "BK1") (pin "10") (pinfunction "TXOP_10") (pintype "passive"))
      (node (ref "C15") (pin "1") (pinfunction "1_1") (pintype "passive"))
      (node (ref "L2") (pin "1") (pinfunction "1_1") (pintype "passive"))
    )
    (net (code "35") (name "Net-(BK1-VCCTX)") (class "Default")
      (node (ref "BK1") (pin "7") (pinfunction "VCCTX_7") (pintype "passive"))
      (node (ref "FB1") (pin "2") (pinfunction "2_2") (pintype "passive"))
    )
    (net (code "36") (name "Net-(BK1-VDDDIG)") (class "Default")
      (node (ref "BK1") (pin "17") (pinfunction "VDDDIG_17") (pintype "passive"))
      (node (ref "C31") (pin "2") (pinfunction "2_2") (pintype "passive"))
    )
    (net (code "37") (name "Net-(BK1-VDDVCO)") (class "Default")
      (node (ref "BK1") (pin "1") (pinfunction "VDDVCO_1") (pintype "passive"))
      (node (ref "C6") (pin "2") (pinfunction "2_2") (pintype "passive"))
    )
    (net (code "38") (name "Net-(BK1-XI)") (class "Default")
      (node (ref "BK1") (pin "31") (pinfunction "XI_31") (pintype "passive"))
      (node (ref "C19") (pin "1") (pinfunction "1_1") (pintype "passive"))
      (node (ref "Y1") (pin "1") (pinfunction "OSC1_1") (pintype "passive"))
    )
    (net (code "39") (name "Net-(BK1-XO)") (class "Default")
      (node (ref "BK1") (pin "30") (pinfunction "XO_30") (pintype "passive"))
      (node (ref "C20") (pin "1") (pinfunction "1_1") (pintype "passive"))
      (node (ref "Y1") (pin "2") (pinfunction "OSC2_2") (pintype "passive"))
    )
    (net (code "40") (name "Net-(C1-Pad2)") (class "Default")
      (node (ref "C1") (pin "2") (pinfunction "2_2") (pintype "passive"))
      (node (ref "C2") (pin "2") (pinfunction "2_2") (pintype "passive"))
      (node (ref "FB1") (pin "1") (pinfunction "1_1") (pintype "passive"))
      (node (ref "L1") (pin "2") (pinfunction "2_2") (pintype "passive"))
      (node (ref "L2") (pin "2") (pinfunction "2_2") (pintype "passive"))
    )
    (net (code "41") (name "Net-(C7-Pad2)") (class "Default")
      (node (ref "C7") (pin "2") (pinfunction "2_2") (pintype "passive"))
      (node (ref "C9") (pin "2") (pinfunction "2_2") (pintype "passive"))
      (node (ref "L4") (pin "2") (pinfunction "2_2") (pintype "passive"))
    )
    (net (code "42") (name "Net-(C14-Pad1)") (class "Default")
      (node (ref "C14") (pin "1") (pinfunction "1_1") (pintype "passive"))
      (node (ref "C15") (pin "2") (pinfunction "2_2") (pintype "passive"))
      (node (ref "L5") (pin "2") (pinfunction "2_2") (pintype "passive"))
    )
    (net (code "43") (name "Net-(C14-Pad2)") (class "Default")
      (node (ref "C14") (pin "2") (pinfunction "2_2") (pintype "passive"))
      (node (ref "C8") (pin "1") (pinfunction "1_1") (pintype "passive"))
      (node (ref "L4") (pin "1") (pinfunction "1_1") (pintype "passive"))
    )
    (net (code "44") (name "Net-(C17-Pad1)") (class "Default")
      (node (ref "C17") (pin "1") (pinfunction "1_1") (pintype "passive"))
      (node (ref "C8") (pin "2") (pinfunction "2_2") (pintype "passive"))
      (node (ref "L3") (pin "2") (pinfunction "2_2") (pintype "passive"))
    )
    (net (code "45") (name "Net-(D1-K)") (class "Default")
      (node (ref "D1") (pin "2") (pinfunction "K_2") (pintype "passive"))
      (node (ref "Q1") (pin "3") (pinfunction "C_3") (pintype "passive"))
      (node (ref "R8") (pin "2") (pinfunction "2_2") (pintype "passive"))
    )
    (net (code "46") (name "Net-(IC1-SCL)") (class "Default")
      (node (ref "IC1") (pin "6") (pinfunction "SCL_6") (pintype "input"))
      (node (ref "R23") (pin "1") (pinfunction "1_1") (pintype "passive"))
      (node (ref "U3") (pin "18") (pinfunction "I2C_SCL_18") (pintype "passive"))
    )
    (net (code "47") (name "Net-(IC1-SDA)") (class "Default")
      (node (ref "IC1") (pin "5") (pinfunction "SDA_5") (pintype "bidirectional"))
      (node (ref "R24") (pin "1") (pinfunction "1_1") (pintype "passive"))
      (node (ref "U3") (pin "19") (pinfunction "I2C_SDA_19") (pintype "passive"))
    )
    (net (code "48") (name "Net-(LED1-A)") (class "Default")
      (node (ref "LED1") (pin "1") (pinfunction "A_1") (pintype "passive"))
      (node (ref "R2") (pin "1") (pinfunction "1_1") (pintype "passive"))
    )
    (net (code "49") (name "Net-(LED2-A)") (class "Default")
      (node (ref "LED2") (pin "1") (pinfunction "A_1") (pintype "passive"))
      (node (ref "R22") (pin "1") (pinfunction "1_1") (pintype "passive"))
    )
    (net (code "50") (name "Net-(LED3-A)") (class "Default")
      (node (ref "LED3") (pin "1") (pinfunction "A_1") (pintype "passive"))
      (node (ref "R28") (pin "1") (pinfunction "1_1") (pintype "passive"))
    )
    (net (code "51") (name "Net-(LED4-A)") (class "Default")
      (node (ref "LED4") (pin "1") (pinfunction "A_1") (pintype "passive"))
      (node (ref "R31") (pin "1") (pinfunction "1_1") (pintype "passive"))
    )
    (net (code "52") (name "Net-(LED4-K)") (class "Default")
      (node (ref "LED4") (pin "2") (pinfunction "K_2") (pintype "passive"))
      (node (ref "Q3") (pin "3") (pinfunction "D_3") (pintype "passive"))
    )
    (net (code "53") (name "Net-(Q1-B)") (class "Default")
      (node (ref "Q1") (pin "1") (pinfunction "B_1") (pintype "passive"))
      (node (ref "R9") (pin "2") (pinfunction "2_2") (pintype "passive"))
    )
    (net (code "54") (name "Net-(Q2-B)") (class "Default")
      (node (ref "Q2") (pin "1") (pinfunction "B_1") (pintype "passive"))
      (node (ref "R10") (pin "2") (pinfunction "2_2") (pintype "passive"))
    )
    (net (code "55") (name "Net-(Q2-C)") (class "Default")
      (node (ref "Q2") (pin "3") (pinfunction "C_3") (pintype "passive"))
      (node (ref "R11") (pin "1") (pinfunction "1_1") (pintype "passive"))
    )
    (net (code "56") (name "Net-(Q3-G)") (class "Default")
      (node (ref "Q3") (pin "1") (pinfunction "G_1") (pintype "passive"))
      (node (ref "R29") (pin "1") (pinfunction "1_1") (pintype "passive"))
      (node (ref "R30") (pin "2") (pinfunction "2_2") (pintype "passive"))
    )
    (net (code "57") (name "Net-(U1A-PA3)") (class "Default")
      (node (ref "R29") (pin "2") (pinfunction "2_2") (pintype "passive"))
      (node (ref "U1") (pin "13") (pinfunction "PA3_13") (pintype "bidirectional"))
    )
    (net (code "58") (name "Net-(U1A-PB0)") (class "Default")
      (node (ref "C3") (pin "2") (pinfunction "2_2") (pintype "passive"))
      (node (ref "R1") (pin "1") (pinfunction "1_1") (pintype "passive"))
      (node (ref "SW1") (pin "1") (pinfunction "1_1") (pintype "passive"))
      (node (ref "U1") (pin "18") (pinfunction "PB0_18") (pintype "bidirectional"))
    )
    (net (code "59") (name "Net-(U1A-PB2)") (class "Default")
      (node (ref "R3") (pin "1") (pinfunction "1_1") (pintype "passive"))
      (node (ref "U1") (pin "20") (pinfunction "PB2_20") (pintype "bidirectional"))
    )
    (net (code "60") (name "Net-(U1A-PD0-OSC_IN)") (class "Default")
      (node (ref "C26") (pin "2") (pinfunction "2_2") (pintype "passive"))
      (node (ref "U1") (pin "5") (pinfunction "PD0-OSC_IN_5") (pintype "bidirectional"))
      (node (ref "Y2") (pin "2") (pinfunction "OSC2_2") (pintype "passive"))
    )
    (net (code "61") (name "Net-(U1A-PD1)") (class "Default")
      (node (ref "C27") (pin "2") (pinfunction "2_2") (pintype "passive"))
      (node (ref "U1") (pin "6") (pinfunction "PD1_6") (pintype "bidirectional"))
      (node (ref "Y2") (pin "1") (pinfunction "OSC1_1") (pintype "passive"))
    )
    (net (code "62") (name "Net-(U3-CFLYN)") (class "Default")
      (node (ref "C38") (pin "1") (pinfunction "1_1") (pintype "passive"))
      (node (ref "U3") (pin "43") (pinfunction "CFLYN_43") (pintype "passive"))
    )
    (net (code "63") (name "Net-(U3-CFLYP)") (class "Default")
      (node (ref "C38") (pin "2") (pinfunction "2_2") (pintype "passive"))
      (node (ref "U3") (pin "45") (pinfunction "CFLYP_45") (pintype "passive"))
    )
    (net (code "64") (name "Net-(U3-HPVDD)") (class "Default")
      (node (ref "C42") (pin "2") (pinfunction "2_2") (pintype "passive"))
      (node (ref "U3") (pin "40") (pinfunction "HPVDD_40") (pintype "passive"))
      (node (ref "U3") (pin "41") (pinfunction "VCPP_41") (pintype "passive"))
    )
    (net (code "65") (name "Net-(U3-HPVSS)") (class "Default")
      (node (ref "C40") (pin "2") (pinfunction "2_2") (pintype "passive"))
      (node (ref "U3") (pin "37") (pinfunction "HPVSS_37") (pintype "passive"))
      (node (ref "U3") (pin "42") (pinfunction "VCPN_42") (pintype "passive"))
    )
    (net (code "66") (name "Net-(U3-INSEL)") (class "Default")
      (node (ref "R27") (pin "1") (pinfunction "1_1") (pintype "passive"))
      (node (ref "U3") (pin "9") (pinfunction "INSEL_9") (pintype "passive"))
    )
    (net (code "67") (name "Net-(U3-KEY_RENC_INV)") (class "Default")
      (node (ref "R15") (pin "1") (pinfunction "1_1") (pintype "passive"))
      (node (ref "U3") (pin "7") (pinfunction "KEY_RENC_INV_7") (pintype "passive"))
    )
    (net (code "68") (name "Net-(U3-LEDO)") (class "Default")
      (node (ref "R22") (pin "2") (pinfunction "2_2") (pintype "passive"))
      (node (ref "U3") (pin "8") (pinfunction "LEDO_8") (pintype "passive"))
    )
    (net (code "69") (name "Net-(U3-STEREO_MIC)") (class "Default")
      (node (ref "R17") (pin "1") (pinfunction "1_1") (pintype "passive"))
      (node (ref "U3") (pin "13") (pinfunction "STEREO_MIC_13") (pintype "passive"))
    )
    (net (code "70") (name "Net-(U3-TEST)") (class "Default")
      (node (ref "R14") (pin "1") (pinfunction "1_1") (pintype "passive"))
      (node (ref "U3") (pin "47") (pinfunction "TEST_47") (pintype "passive"))
    )
    (net (code "71") (name "Net-(U3-V12)") (class "Default")
      (node (ref "C41") (pin "2") (pinfunction "2_2") (pintype "passive"))
      (node (ref "U3") (pin "4") (pinfunction "V12_4") (pintype "passive"))
    )
    (net (code "72") (name "Net-(U3-VMID)") (class "Default")
      (node (ref "C43") (pin "2") (pinfunction "2_2") (pintype "passive"))
      (node (ref "C44") (pin "2") (pinfunction "2_2") (pintype "passive"))
      (node (ref "U3") (pin "35") (pinfunction "VMID_35") (pintype "passive"))
    )
    (net (code "73") (name "Net-(USBC1-CC1)") (class "Default")
      (node (ref "R25") (pin "2") (pinfunction "2_2") (pintype "passive"))
      (node (ref "USBC1") (pin "A5") (pinfunction "CC1_A5") (pintype "passive"))
    )
    (net (code "74") (name "Net-(USBC1-CC2)") (class "Default")
      (node (ref "R26") (pin "1") (pinfunction "1_1") (pintype "passive"))
      (node (ref "USBC1") (pin "B5") (pinfunction "CC2_B5") (pintype "passive"))
    )
    (net (code "75") (name "RF3V3") (class "Default")
      (node (ref "BK1") (pin "13") (pinfunction "VCCAUD_13") (pintype "passive"))
      (node (ref "BK1") (pin "16") (pinfunction "VCCDIG_16") (pintype "passive"))
      (node (ref "BK1") (pin "2") (pinfunction "VCCVCO_2") (pintype "passive"))
      (node (ref "BK1") (pin "24") (pinfunction "VCCIF_24") (pintype "passive"))
      (node (ref "BK1") (pin "28") (pinfunction "VCCDVCO_28") (pintype "passive"))
      (node (ref "BK1") (pin "29") (pinfunction "VCCXTAL_29") (pintype "passive"))
      (node (ref "BK1") (pin "32") (pinfunction "VCCPLL_32") (pintype "passive"))
      (node (ref "BK1") (pin "4") (pinfunction "VCCB_4") (pintype "passive"))
      (node (ref "BK1") (pin "8") (pinfunction "VCCPA_8") (pintype "passive"))
      (node (ref "C18") (pin "1") (pinfunction "1_1") (pintype "passive"))
      (node (ref "C22") (pin "2") (pinfunction "2_2") (pintype "passive"))
      (node (ref "C25") (pin "1") (pinfunction "1_1") (pintype "passive"))
      (node (ref "C30") (pin "2") (pinfunction "2_2") (pintype "passive"))
      (node (ref "C32") (pin "2") (pinfunction "2_2") (pintype "passive"))
      (node (ref "C4") (pin "2") (pinfunction "2_2") (pintype "passive"))
      (node (ref "C5") (pin "2") (pinfunction "2_2") (pintype "passive"))
      (node (ref "C53") (pin "1") (pinfunction "1_1") (pintype "passive"))
      (node (ref "U4") (pin "5") (pinfunction "VOUT_5") (pintype "passive"))
    )
    (net (code "76") (name "USB_5V") (class "Default")
      (node (ref "C23") (pin "1") (pinfunction "1_1") (pintype "passive"))
      (node (ref "C49") (pin "2") (pinfunction "2_2") (pintype "passive"))
      (node (ref "C52") (pin "1") (pinfunction "1_1") (pintype "passive"))
      (node (ref "FB5") (pin "1") (pinfunction "1_1") (pintype "passive"))
      (node (ref "U2") (pin "3") (pinfunction "Vin_3") (pintype "passive"))
      (node (ref "U4") (pin "1") (pinfunction "VIN_1") (pintype "passive"))
    )
    (net (code "77") (name "VBUS") (class "Default")
      (node (ref "C50") (pin "2") (pinfunction "2_2") (pintype "passive"))
      (node (ref "C51") (pin "2") (pinfunction "2_2") (pintype "passive"))
      (node (ref "FB5") (pin "2") (pinfunction "2_2") (pintype "passive"))
      (node (ref "U3") (pin "1") (pinfunction "VBUS_1") (pintype "passive"))
      (node (ref "USBC1") (pin "A4") (pinfunction "VBUS_A4") (pintype "passive"))
      (node (ref "USBC1") (pin "A9") (pinfunction "VBUS_A9") (pintype "passive"))
      (node (ref "USBC1") (pin "B4") (pinfunction "VBUS_B4") (pintype "passive"))
      (node (ref "USBC1") (pin "B9") (pinfunction "VBUS_B9") (pintype "passive"))
    )
    (net (code "78") (name "VDDA") (class "Default")
      (node (ref "C12") (pin "2") (pinfunction "2_2") (pintype "passive"))
      (node (ref "C13") (pin "2") (pinfunction "2_2") (pintype "passive"))
      (node (ref "FB2") (pin "2") (pinfunction "2_2") (pintype "passive"))
      (node (ref "U1") (pin "9") (pinfunction "VDDA_9") (pintype "power_in"))
    )
    (net (code "79") (name "VSSA") (class "Default")
      (node (ref "C12") (pin "1") (pinfunction "1_1") (pintype "passive"))
      (node (ref "C13") (pin "1") (pinfunction "1_1") (pintype "passive"))
      (node (ref "FB3") (pin "2") (pinfunction "2_2") (pintype "passive"))
      (node (ref "U1") (pin "8") (pinfunction "VSSA_8") (pintype "power_in"))
    )
    (net (code "80") (name "unconnected-(BK1-GPIO2-Pad20)") (class "Default")
      (node (ref "BK1") (pin "20") (pinfunction "GPIO2_20") (pintype "passive"))
    )
    (net (code "81") (name "unconnected-(BK1-GPIO4-Pad25)") (class "Default")
      (node (ref "BK1") (pin "25") (pinfunction "GPIO4_25") (pintype "passive+no_connect"))
    )
    (net (code "82") (name "unconnected-(BK1-IRQ-Pad27)") (class "Default")
      (node (ref "BK1") (pin "27") (pinfunction "IRQ_27") (pintype "passive+no_connect"))
    )
    (net (code "83") (name "unconnected-(BK1-MICN-Pad14)") (class "Default")
      (node (ref "BK1") (pin "14") (pinfunction "MICN_14") (pintype "passive+no_connect"))
    )
    (net (code "84") (name "unconnected-(BK1-MICP-Pad15)") (class "Default")
      (node (ref "BK1") (pin "15") (pinfunction "MICP_15") (pintype "passive+no_connect"))
    )
    (net (code "85") (name "unconnected-(BK1-NC-Pad5)") (class "Default")
      (node (ref "BK1") (pin "5") (pinfunction "NC_5") (pintype "passive"))
    )
    (net (code "86") (name "unconnected-(BK1-NC-Pad6)") (class "Default")
      (node (ref "BK1") (pin "6") (pinfunction "NC_6") (pintype "passive"))
    )
    (net (code "87") (name "unconnected-(IC1-WP-Pad7)") (class "Default")
      (node (ref "IC1") (pin "7") (pinfunction "WP_7") (pintype "passive+no_connect"))
    )
    (net (code "88") (name "unconnected-(U1A-PA0-WKUP-Pad10)") (class "Default")
      (node (ref "U1") (pin "10") (pinfunction "PA0-WKUP_10") (pintype "bidirectional"))
    )
    (net (code "89") (name "unconnected-(U1A-PA1-Pad11)") (class "Default")
      (node (ref "U1") (pin "11") (pinfunction "PA1_11") (pintype "bidirectional"))
    )
    (net (code "90") (name "unconnected-(U1A-PA2-Pad12)") (class "Default")
      (node (ref "U1") (pin "12") (pinfunction "PA2_12") (pintype "bidirectional"))
    )
    (net (code "91") (name "unconnected-(U1A-PA4-Pad14)") (class "Default")
      (node (ref "U1") (pin "14") (pinfunction "PA4_14") (pintype "bidirectional"))
    )
    (net (code "92") (name "unconnected-(U1A-PA8-Pad29)") (class "Default")
      (node (ref "U1") (pin "29") (pinfunction "PA8_29") (pintype "bidirectional"))
    )
    (net (code "93") (name "unconnected-(U1A-PA11-Pad32)") (class "Default")
      (node (ref "U1") (pin "32") (pinfunction "PA11_32") (pintype "bidirectional"))
    )
    (net (code "94") (name "unconnected-(U1A-PA12-Pad33)") (class "Default")
      (node (ref "U1") (pin "33") (pinfunction "PA12_33") (pintype "bidirectional"))
    )
    (net (code "95") (name "unconnected-(U1A-PA15-Pad38)") (class "Default")
      (node (ref "U1") (pin "38") (pinfunction "PA15_38") (pintype "bidirectional"))
    )
    (net (code "96") (name "unconnected-(U1A-PB1-Pad19)") (class "Default")
      (node (ref "U1") (pin "19") (pinfunction "PB1_19") (pintype "bidirectional"))
    )
    (net (code "97") (name "unconnected-(U1A-PB3-Pad39)") (class "Default")
      (node (ref "U1") (pin "39") (pinfunction "PB3_39") (pintype "bidirectional"))
    )
    (net (code "98") (name "unconnected-(U1A-PB5-Pad41)") (class "Default")
      (node (ref "U1") (pin "41") (pinfunction "PB5_41") (pintype "bidirectional"))
    )
    (net (code "99") (name "unconnected-(U1A-PB8-Pad45)") (class "Default")
      (node (ref "U1") (pin "45") (pinfunction "PB8_45") (pintype "bidirectional"))
    )
    (net (code "100") (name "unconnected-(U1A-PB9-Pad46)") (class "Default")
      (node (ref "U1") (pin "46") (pinfunction "PB9_46") (pintype "bidirectional"))
    )
    (net (code "101") (name "unconnected-(U1A-PB10-Pad21)") (class "Default")
      (node (ref "U1") (pin "21") (pinfunction "PB10_21") (pintype "bidirectional"))
    )
    (net (code "102") (name "unconnected-(U1A-PB11-Pad22)") (class "Default")
      (node (ref "U1") (pin "22") (pinfunction "PB11_22") (pintype "bidirectional"))
    )
    (net (code "103") (name "unconnected-(U1A-PB12-Pad25)") (class "Default")
      (node (ref "U1") (pin "25") (pinfunction "PB12_25") (pintype "bidirectional"))
    )
    (net (code "104") (name "unconnected-(U1A-PB14-Pad27)") (class "Default")
      (node (ref "U1") (pin "27") (pinfunction "PB14_27") (pintype "bidirectional"))
    )
    (net (code "105") (name "unconnected-(U1A-PB15-Pad28)") (class "Default")
      (node (ref "U1") (pin "28") (pinfunction "PB15_28") (pintype "bidirectional"))
    )
    (net (code "106") (name "unconnected-(U1A-PC13-TAMPER-RTC-Pad2)") (class "Default")
      (node (ref "U1") (pin "2") (pinfunction "PC13-TAMPER-RTC_2") (pintype "bidirectional"))
    )
    (net (code "107") (name "unconnected-(U1A-PC14-OSC32_IN-Pad3)") (class "Default")
      (node (ref "U1") (pin "3") (pinfunction "PC14-OSC32_IN_3") (pintype "bidirectional"))
    )
    (net (code "108") (name "unconnected-(U1A-PC15-OSC32_OUT-Pad4)") (class "Default")
      (node (ref "U1") (pin "4") (pinfunction "PC15-OSC32_OUT_4") (pintype "bidirectional"))
    )
    (net (code "109") (name "unconnected-(U3-EQ3D_LED-Pad48)") (class "Default")
      (node (ref "U3") (pin "48") (pinfunction "EQ3D_LED_48") (pintype "passive+no_connect"))
    )
    (net (code "110") (name "unconnected-(U3-LHPOUT-Pad39)") (class "Default")
      (node (ref "U3") (pin "39") (pinfunction "LHPOUT_39") (pintype "passive+no_connect"))
    )
    (net (code "111") (name "unconnected-(U3-MIC1-Pad29)") (class "Default")
      (node (ref "U3") (pin "29") (pinfunction "MIC1_29") (pintype "passive+no_connect"))
    )
    (net (code "112") (name "unconnected-(U3-MIC1N-Pad31)") (class "Default")
      (node (ref "U3") (pin "31") (pinfunction "MIC1N_31") (pintype "passive+no_connect"))
    )
    (net (code "113") (name "unconnected-(U3-MIC1P-Pad32)") (class "Default")
      (node (ref "U3") (pin "32") (pinfunction "MIC1P_32") (pintype "passive+no_connect"))
    )
    (net (code "114") (name "unconnected-(U3-MIC2P-Pad33)") (class "Default")
      (node (ref "U3") (pin "33") (pinfunction "MIC2P_33") (pintype "passive+no_connect"))
    )
    (net (code "115") (name "unconnected-(U3-MICBIAS-Pad30)") (class "Default")
      (node (ref "U3") (pin "30") (pinfunction "MICBIAS_30") (pintype "passive+no_connect"))
    )
    (net (code "116") (name "unconnected-(U3-MSEL-Pad10)") (class "Default")
      (node (ref "U3") (pin "10") (pinfunction "MSEL_10") (pintype "passive+no_connect"))
    )
    (net (code "117") (name "unconnected-(U3-NEXT_TRACK-Pad20)") (class "Default")
      (node (ref "U3") (pin "20") (pinfunction "NEXT_TRACK_20") (pintype "passive+no_connect"))
    )
    (net (code "118") (name "unconnected-(U3-PALY_PAUSE-Pad22)") (class "Default")
      (node (ref "U3") (pin "22") (pinfunction "PALY_PAUSE_22") (pintype "passive+no_connect"))
    )
    (net (code "119") (name "unconnected-(U3-PLAY_EN-Pad16)") (class "Default")
      (node (ref "U3") (pin "16") (pinfunction "PLAY_EN_16") (pintype "passive+no_connect"))
    )
    (net (code "120") (name "unconnected-(U3-PRE_TACK-Pad21)") (class "Default")
      (node (ref "U3") (pin "21") (pinfunction "PRE_TACK_21") (pintype "passive+no_connect"))
    )
    (net (code "121") (name "unconnected-(U3-REC_EN-Pad17)") (class "Default")
      (node (ref "U3") (pin "17") (pinfunction "REC_EN_17") (pintype "passive+no_connect"))
    )
    (net (code "122") (name "unconnected-(U3-RHPOUT-Pad38)") (class "Default")
      (node (ref "U3") (pin "38") (pinfunction "RHPOUT_38") (pintype "passive+no_connect"))
    )
    (net (code "123") (name "unconnected-(U3-RING2-Pad28)") (class "Default")
      (node (ref "U3") (pin "28") (pinfunction "RING2_28") (pintype "passive+no_connect"))
    )
    (net (code "124") (name "unconnected-(U3-SLEEVE-Pad26)") (class "Default")
      (node (ref "U3") (pin "26") (pinfunction "SLEEVE_26") (pintype "passive+no_connect"))
    )
    (net (code "125") (name "unconnected-(U3-STOP-Pad24)") (class "Default")
      (node (ref "U3") (pin "24") (pinfunction "STOP_24") (pintype "passive+no_connect"))
    )
    (net (code "126") (name "unconnected-(U3-VOLDN-Pad15)") (class "Default")
      (node (ref "U3") (pin "15") (pinfunction "VOLDN_15") (pintype "passive+no_connect"))
    )
    (net (code "127") (name "unconnected-(U3-VP_MUTE-Pad25)") (class "Default")
      (node (ref "U3") (pin "25") (pinfunction "VP_MUTE_25") (pintype "passive+no_connect"))
    )
    (net (code "128") (name "unconnected-(U3-VR_MUTE-Pad23)") (class "Default")
      (node (ref "U3") (pin "23") (pinfunction "VR_MUTE_23") (pintype "passive+no_connect"))
    )
    (net (code "129") (name "unconnected-(U4-NC-Pad4)") (class "Default")
      (node (ref "U4") (pin "4") (pinfunction "NC_4") (pintype "passive+no_connect"))
    )
    (net (code "130") (name "unconnected-(USBC1-SBU1-PadA8)") (class "Default")
      (node (ref "USBC1") (pin "A8") (pinfunction "SBU1_A8") (pintype "passive"))
    )
    (net (code "131") (name "unconnected-(USBC1-SBU2-PadB8)") (class "Default")
      (node (ref "USBC1") (pin "B8") (pinfunction "SBU2_B8") (pintype "passive"))
    )
  )
)
